# SCH.net
KiCad netlist of a schematic drawn in EasyEDA
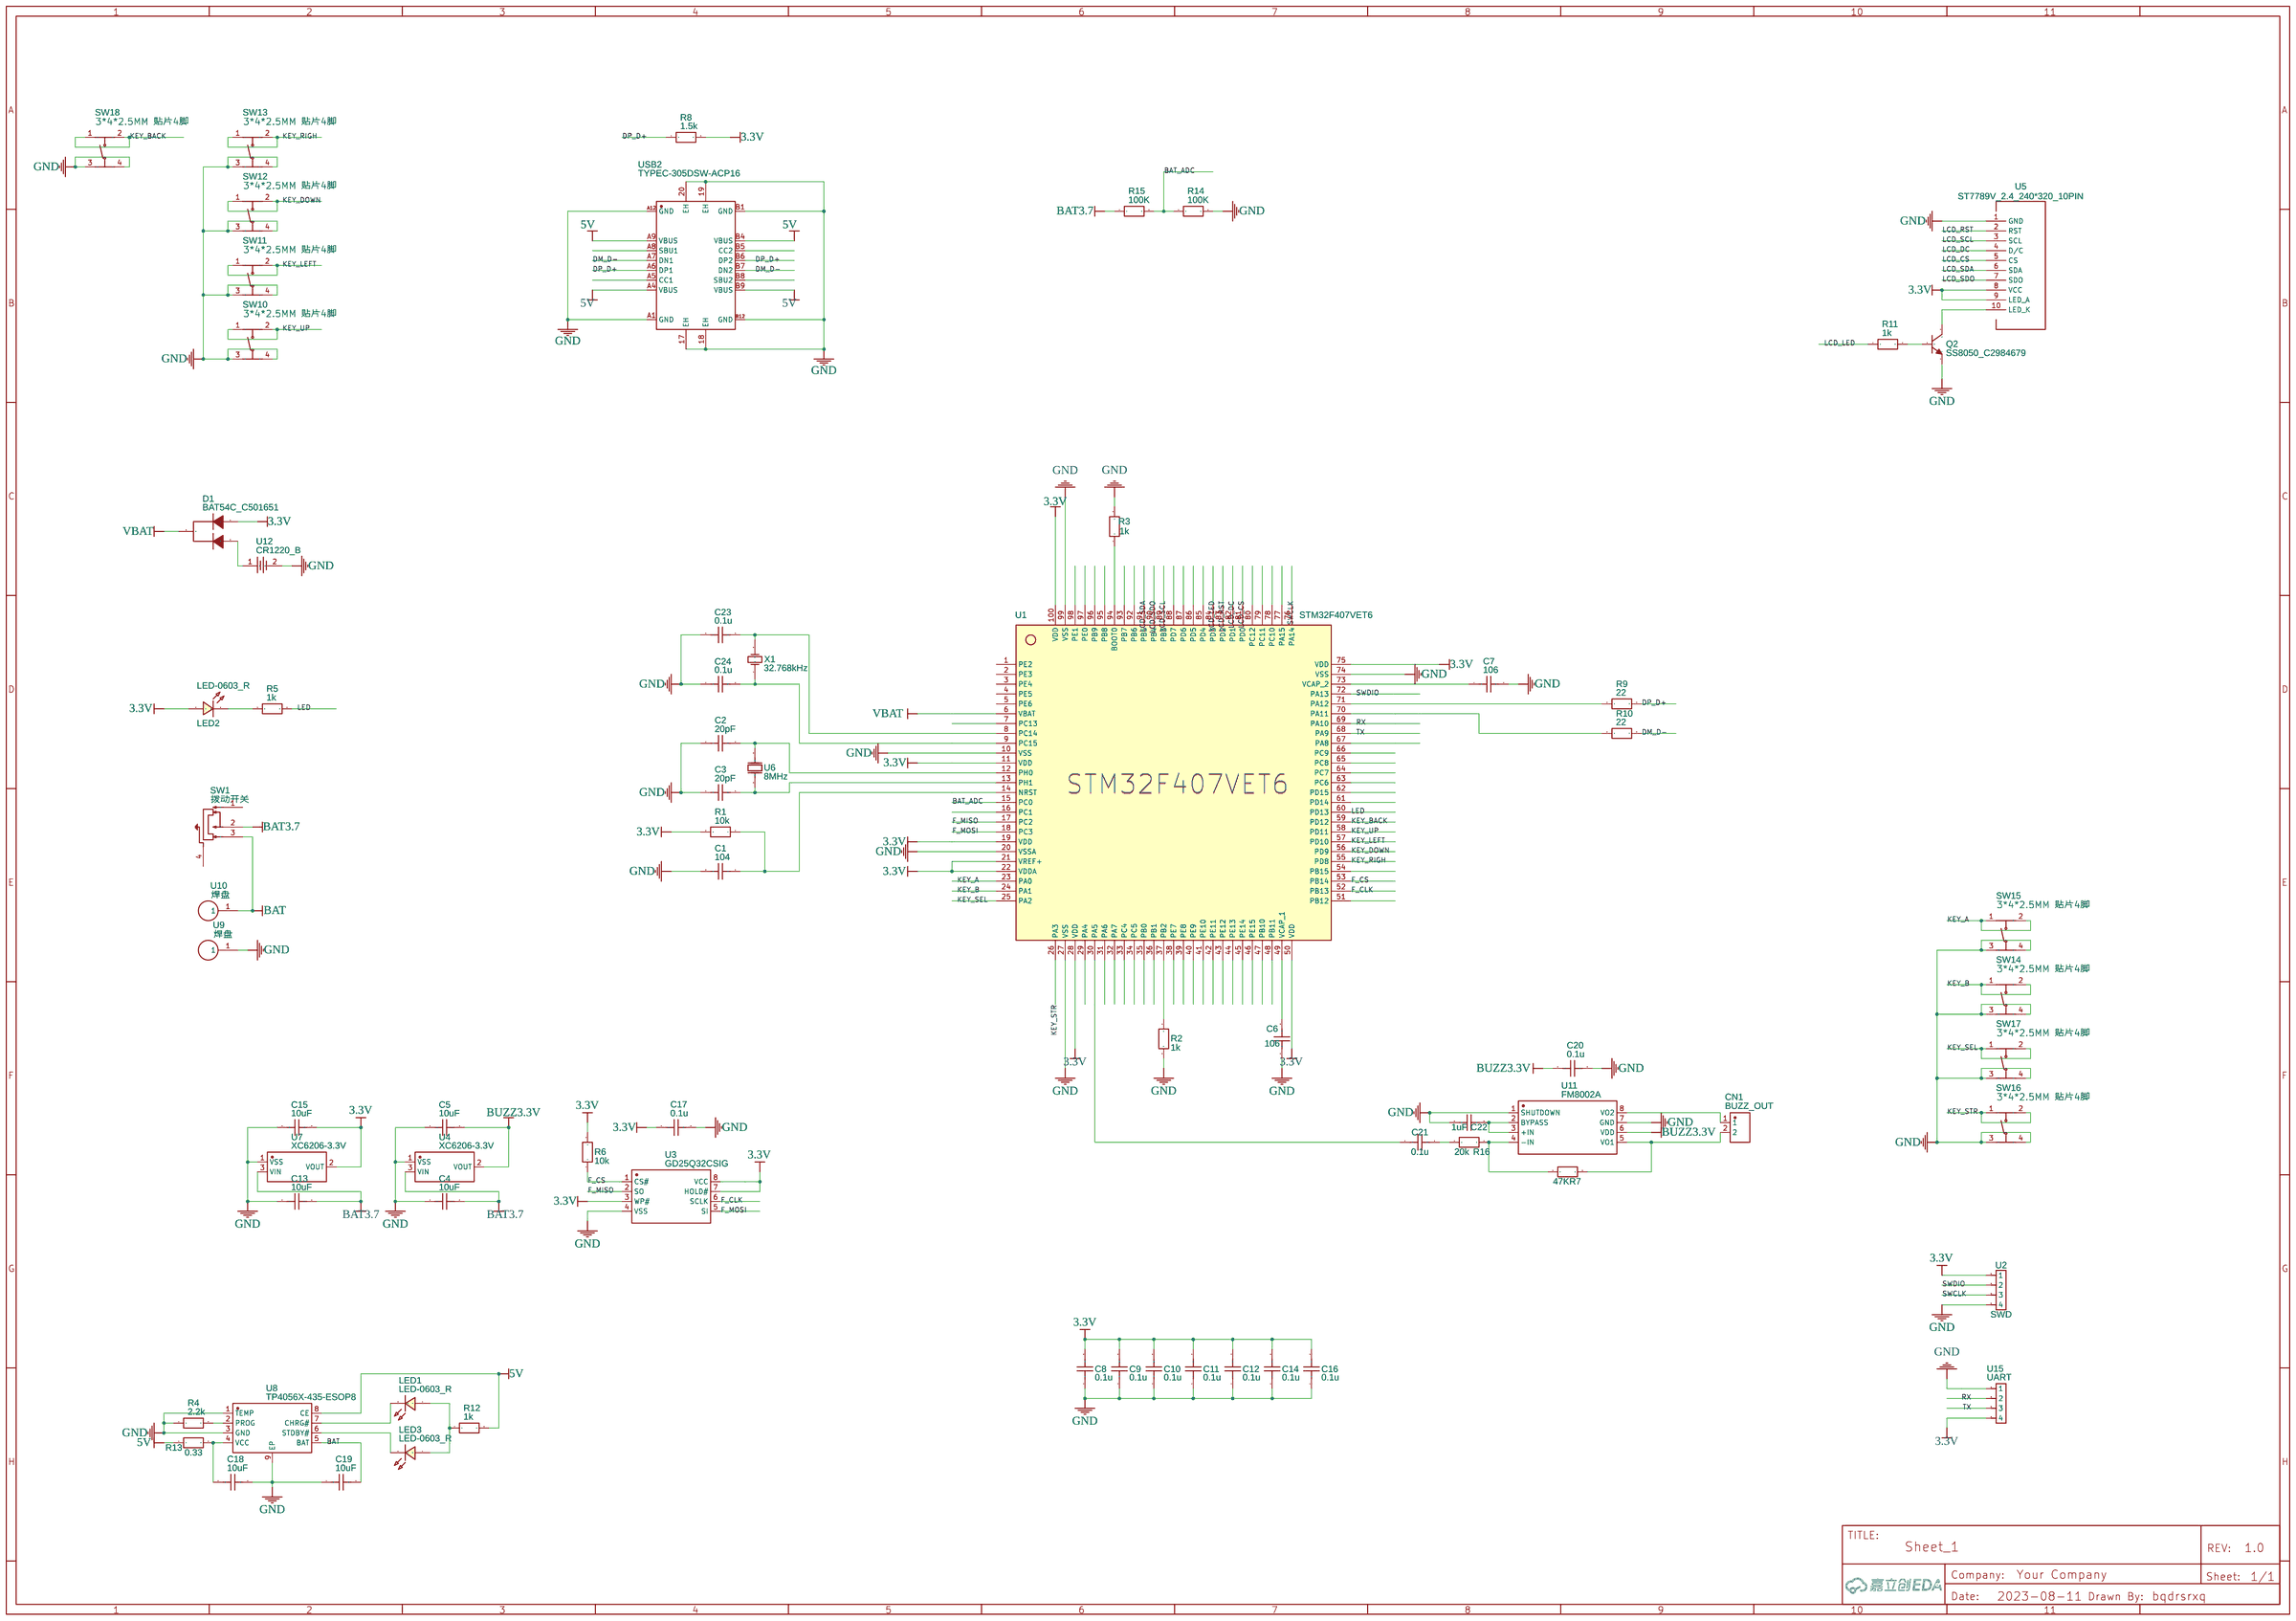
[diagram p0: schematic sheet]

(export (version "E")
  (design (tool "Eeschema 10.0.6"))
  (components
    (comp (ref "C1") (value "104") (libsource (lib "") (part "C_0603_US_2")))
    (comp (ref "C2") (value "20pF") (libsource (lib "") (part "C_0603_US")))
    (comp (ref "C3") (value "20pF") (libsource (lib "") (part "C_0603_US")))
    (comp (ref "C4") (value "10uF") (libsource (lib "") (part "C_0603_US")))
    (comp (ref "C5") (value "10uF") (libsource (lib "") (part "C_0603_US")))
    (comp (ref "C6") (value "106") (libsource (lib "") (part "C_0603_US_1")))
    (comp (ref "C7") (value "106") (libsource (lib "") (part "C_0603_US")))
    (comp (ref "C8") (value "0.1u") (libsource (lib "") (part "C_0603_US_1")))
    (comp (ref "C9") (value "0.1u") (libsource (lib "") (part "C_0603_US_1")))
    (comp (ref "C10") (value "0.1u") (libsource (lib "") (part "C_0603_US_1")))
    (comp (ref "C11") (value "0.1u") (libsource (lib "") (part "C_0603_US_1")))
    (comp (ref "C12") (value "0.1u") (libsource (lib "") (part "C_0603_US_1")))
    (comp (ref "C13") (value "10uF") (libsource (lib "") (part "C_0603_US")))
    (comp (ref "C14") (value "0.1u") (libsource (lib "") (part "C_0603_US_1")))
    (comp (ref "C15") (value "10uF") (libsource (lib "") (part "C_0603_US")))
    (comp (ref "C16") (value "0.1u") (libsource (lib "") (part "C_0603_US_1")))
    (comp (ref "C17") (value "0.1u") (libsource (lib "") (part "C_0603_US")))
    (comp (ref "C18") (value "10uF") (libsource (lib "") (part "C_0603_US")))
    (comp (ref "C19") (value "10uF") (libsource (lib "") (part "C_0603_US")))
    (comp (ref "C20") (value "0.1u") (libsource (lib "") (part "C_0603_US")))
    (comp (ref "C21") (value "0.1u") (libsource (lib "") (part "C_0603_US")))
    (comp (ref "C22") (value "1uF") (libsource (lib "") (part "C_0603_US")))
    (comp (ref "C23") (value "0.1u") (libsource (lib "") (part "C_0603_US")))
    (comp (ref "C24") (value "0.1u") (libsource (lib "") (part "C_0603_US")))
    (comp (ref "CN1")
      (value "BUZZ_OUT")
      (fields (field (name "Manufacturer Part") "CON2-2.54*2P"))
      (libsource (lib "") (part "CON2-2.54*2P"))
    )
    (comp (ref "D1")
      (value "BAT54C_C501651")
      (fields (field (name "Manufacturer Part") "BAT54C") (field (name "Manufacturer") "JF(吉福)"))
      (libsource (lib "") (part "BAT54C_C501651"))
    )
    (comp (ref "LED1")
      (value "LED-0603_R")
      (fields
        (field (name "BOM_Manufacturer Part") "19-217/R6C-AL1M2VY/3T")
        (field (name "BOM_Supplier Part") "C72044")
      )
      (libsource (lib "") (part "LED-0603_R_1"))
    )
    (comp (ref "LED2")
      (value "LED-0603_R")
      (fields
        (field (name "BOM_Manufacturer Part") "19-217/R6C-AL1M2VY/3T")
        (field (name "BOM_Supplier Part") "C72044")
      )
      (libsource (lib "") (part "LED-0603_R"))
    )
    (comp (ref "LED3")
      (value "LED-0603_R")
      (fields
        (field (name "BOM_Manufacturer Part") "19-217/R6C-AL1M2VY/3T")
        (field (name "BOM_Supplier Part") "C72044")
      )
      (libsource (lib "") (part "LED-0603_R_1"))
    )
    (comp (ref "Q2")
      (value "SS8050_C2984679")
      (fields (field (name "Manufacturer Part") "SS8050") (field (name "Manufacturer") "集晶电子"))
      (libsource (lib "") (part "SS8050_C2984679"))
    )
    (comp (ref "R1") (value "10k") (libsource (lib "") (part "R_0603_EU_2")))
    (comp (ref "R2") (value "1k") (libsource (lib "") (part "R_0603_EU_3")))
    (comp (ref "R3") (value "1k") (libsource (lib "") (part "R_0603_EU")))
    (comp (ref "R4") (value "2.2k") (libsource (lib "") (part "R_0603_EU_1")))
    (comp (ref "R5") (value "1k") (libsource (lib "") (part "R_0603_EU_1")))
    (comp (ref "R6") (value "10k") (libsource (lib "") (part "R_0603_EU")))
    (comp (ref "R7") (value "47K") (libsource (lib "") (part "R_0603_EU_1")))
    (comp (ref "R8") (value "1.5k") (libsource (lib "") (part "R_0603_EU_1")))
    (comp (ref "R9") (value "22") (libsource (lib "") (part "R_0603_EU_1")))
    (comp (ref "R10") (value "22") (libsource (lib "") (part "R_0603_EU_1")))
    (comp (ref "R11") (value "1k") (libsource (lib "") (part "R_0603_EU_1")))
    (comp (ref "R12") (value "1k") (libsource (lib "") (part "R_0603_EU_1")))
    (comp (ref "R13") (value "0.33") (libsource (lib "") (part "R_0603_EU_1")))
    (comp (ref "R14") (value "100K") (libsource (lib "") (part "R_0603_EU_1")))
    (comp (ref "R15") (value "100K") (libsource (lib "") (part "R_0603_EU_1")))
    (comp (ref "R16") (value "20k") (libsource (lib "") (part "R_0603_EU_1")))
    (comp (ref "SW1")
      (value "拨动开关")
      (fields
        (field (name "BOM_Manufacturer Part") "HX MSK12C02-BB")
        (field (name "BOM_Supplier Part") "C5149816")
      )
      (libsource (lib "") (part "拨动开关_三脚两档4固定_贴片_侧拨_MSK12C01"))
    )
    (comp (ref "SW10")
      (value "3*4*2.5MM 贴片4脚")
      (fields (field (name "Manufacturer Part") "3*4*2.5mm 贴片4脚"))
      (libsource (lib "") (part "3*4*2.5MM 贴片4脚"))
    )
    (comp (ref "SW11")
      (value "3*4*2.5MM 贴片4脚")
      (fields (field (name "Manufacturer Part") "3*4*2.5mm 贴片4脚"))
      (libsource (lib "") (part "3*4*2.5MM 贴片4脚"))
    )
    (comp (ref "SW12")
      (value "3*4*2.5MM 贴片4脚")
      (fields (field (name "Manufacturer Part") "3*4*2.5mm 贴片4脚"))
      (libsource (lib "") (part "3*4*2.5MM 贴片4脚"))
    )
    (comp (ref "SW13")
      (value "3*4*2.5MM 贴片4脚")
      (fields (field (name "Manufacturer Part") "3*4*2.5mm 贴片4脚"))
      (libsource (lib "") (part "3*4*2.5MM 贴片4脚"))
    )
    (comp (ref "SW14")
      (value "3*4*2.5MM 贴片4脚")
      (fields (field (name "Manufacturer Part") "3*4*2.5mm 贴片4脚"))
      (libsource (lib "") (part "3*4*2.5MM 贴片4脚"))
    )
    (comp (ref "SW15")
      (value "3*4*2.5MM 贴片4脚")
      (fields (field (name "Manufacturer Part") "3*4*2.5mm 贴片4脚"))
      (libsource (lib "") (part "3*4*2.5MM 贴片4脚"))
    )
    (comp (ref "SW16")
      (value "3*4*2.5MM 贴片4脚")
      (fields (field (name "Manufacturer Part") "3*4*2.5mm 贴片4脚"))
      (libsource (lib "") (part "3*4*2.5MM 贴片4脚"))
    )
    (comp (ref "SW17")
      (value "3*4*2.5MM 贴片4脚")
      (fields (field (name "Manufacturer Part") "3*4*2.5mm 贴片4脚"))
      (libsource (lib "") (part "3*4*2.5MM 贴片4脚"))
    )
    (comp (ref "SW18")
      (value "3*4*2.5MM 贴片4脚")
      (fields (field (name "Manufacturer Part") "3*4*2.5mm 贴片4脚"))
      (libsource (lib "") (part "3*4*2.5MM 贴片4脚"))
    )
    (comp (ref "U1") (value "STM32F407VET6") (libsource (lib "") (part "STM32F407VET6")))
    (comp (ref "U2") (value "SWD") (libsource (lib "") (part "CON4")))
    (comp (ref "U3")
      (value "GD25Q32CSIG")
      (fields (field (name "BOM_Supplier Part") "C79075"))
      (libsource (lib "") (part "GD25Q32CSIG"))
    )
    (comp (ref "U4")
      (value "XC6206-3.3V")
      (fields (field (name "BOM_Supplier Part") "C2891841"))
      (libsource (lib "") (part "XC6206-3.3V"))
    )
    (comp (ref "U5")
      (value "ST7789V_2.4_240*320_10PIN")
      (libsource (lib "") (part "ST7789V_2.4_240*320_10PIN"))
    )
    (comp (ref "U6")
      (value "8MHz")
      (fields (field (name "Manufacturer Part") "ATS08ASM-1E") (field (name "Manufacturer") "CTS(西迪斯)"))
      (libsource (lib "") (part "ATS08ASM-1E"))
    )
    (comp (ref "U7")
      (value "XC6206-3.3V")
      (fields (field (name "BOM_Supplier Part") "C2891841"))
      (libsource (lib "") (part "XC6206-3.3V"))
    )
    (comp (ref "U8") (value "TP4056X-435-ESOP8") (libsource (lib "") (part "TP4056X-435-ESOP8")))
    (comp (ref "U9") (value "焊盘") (libsource (lib "") (part "焊盘")))
    (comp (ref "U10") (value "焊盘") (libsource (lib "") (part "焊盘")))
    (comp (ref "U11")
      (value "FM8002A")
      (fields (field (name "Manufacturer") "FM(富满)"))
      (libsource (lib "") (part "FM8002A"))
    )
    (comp (ref "U12") (value "CR1220_B") (libsource (lib "") (part "CR1220_B")))
    (comp (ref "U15") (value "UART") (libsource (lib "") (part "CON4")))
    (comp (ref "USB2")
      (value "TYPEC-305DSW-ACP16")
      (fields (field (name "Manufacturer") "XUNPU(讯普)"))
      (libsource (lib "") (part "TYPEC-305DSW-ACP16"))
    )
    (comp (ref "X1")
      (value "32.768kHz")
      (fields (field (name "Manufacturer Part") "Q2632768PWNAC") (field (name "Manufacturer") "JYJE(晶友嘉)"))
      (libsource (lib "") (part "Q2632768PWNAC"))
    )
  )
  (nets
    (net (code "1") (name "/BAT_ADC") (class "Default")
      (node (ref "R14") (pin "1") (pinfunction "1_1") (pintype "unspecified"))
      (node (ref "R15") (pin "2") (pinfunction "2_2") (pintype "unspecified"))
      (node (ref "U1") (pin "15") (pinfunction "PC0_15") (pintype "unspecified"))
    )
    (net (code "2") (name "/DM_D-") (class "Default")
      (node (ref "R10") (pin "2") (pinfunction "2_2") (pintype "unspecified"))
      (node (ref "USB2") (pin "A7") (pinfunction "DN1_A7") (pintype "unspecified"))
      (node (ref "USB2") (pin "B7") (pinfunction "DN2_B7") (pintype "unspecified"))
    )
    (net (code "3") (name "/DP_D+") (class "Default")
      (node (ref "R8") (pin "1") (pinfunction "1_1") (pintype "unspecified"))
      (node (ref "R9") (pin "2") (pinfunction "2_2") (pintype "unspecified"))
      (node (ref "USB2") (pin "A6") (pinfunction "DP1_A6") (pintype "unspecified"))
      (node (ref "USB2") (pin "B6") (pinfunction "DP2_B6") (pintype "unspecified"))
    )
    (net (code "4") (name "/F_CLK") (class "Default")
      (node (ref "U1") (pin "52") (pinfunction "PB13_52") (pintype "unspecified"))
      (node (ref "U3") (pin "6") (pinfunction "SCLK_6") (pintype "unspecified"))
    )
    (net (code "5") (name "/F_CS") (class "Default")
      (node (ref "R6") (pin "1") (pinfunction "1_1") (pintype "unspecified"))
      (node (ref "U1") (pin "53") (pinfunction "PB14_53") (pintype "unspecified"))
      (node (ref "U3") (pin "1") (pinfunction "CS#_1") (pintype "unspecified"))
    )
    (net (code "6") (name "/F_MISO") (class "Default")
      (node (ref "U1") (pin "17") (pinfunction "PC2_17") (pintype "unspecified"))
      (node (ref "U3") (pin "2") (pinfunction "SO_2") (pintype "unspecified"))
    )
    (net (code "7") (name "/F_MOSI") (class "Default")
      (node (ref "U1") (pin "18") (pinfunction "PC3_18") (pintype "unspecified"))
      (node (ref "U3") (pin "5") (pinfunction "SI_5") (pintype "unspecified"))
    )
    (net (code "8") (name "/KEY_A") (class "Default")
      (node (ref "SW15") (pin "1") (pinfunction "1_1") (pintype "unspecified"))
      (node (ref "SW15") (pin "2") (pinfunction "2_2") (pintype "unspecified"))
      (node (ref "U1") (pin "23") (pinfunction "PA0_23") (pintype "unspecified"))
    )
    (net (code "9") (name "/KEY_B") (class "Default")
      (node (ref "SW14") (pin "1") (pinfunction "1_1") (pintype "unspecified"))
      (node (ref "SW14") (pin "2") (pinfunction "2_2") (pintype "unspecified"))
      (node (ref "U1") (pin "24") (pinfunction "PA1_24") (pintype "unspecified"))
    )
    (net (code "10") (name "/KEY_BACK") (class "Default")
      (node (ref "SW18") (pin "1") (pinfunction "1_1") (pintype "unspecified"))
      (node (ref "SW18") (pin "2") (pinfunction "2_2") (pintype "unspecified"))
      (node (ref "U1") (pin "59") (pinfunction "PD12_59") (pintype "unspecified"))
    )
    (net (code "11") (name "/KEY_DOWN") (class "Default")
      (node (ref "SW12") (pin "1") (pinfunction "1_1") (pintype "unspecified"))
      (node (ref "SW12") (pin "2") (pinfunction "2_2") (pintype "unspecified"))
      (node (ref "U1") (pin "56") (pinfunction "PD9_56") (pintype "unspecified"))
    )
    (net (code "12") (name "/KEY_LEFT") (class "Default")
      (node (ref "SW11") (pin "1") (pinfunction "1_1") (pintype "unspecified"))
      (node (ref "SW11") (pin "2") (pinfunction "2_2") (pintype "unspecified"))
      (node (ref "U1") (pin "57") (pinfunction "PD10_57") (pintype "unspecified"))
    )
    (net (code "13") (name "/KEY_RIGH") (class "Default")
      (node (ref "SW13") (pin "1") (pinfunction "1_1") (pintype "unspecified"))
      (node (ref "SW13") (pin "2") (pinfunction "2_2") (pintype "unspecified"))
      (node (ref "U1") (pin "55") (pinfunction "PD8_55") (pintype "unspecified"))
    )
    (net (code "14") (name "/KEY_SEL") (class "Default")
      (node (ref "SW17") (pin "1") (pinfunction "1_1") (pintype "unspecified"))
      (node (ref "SW17") (pin "2") (pinfunction "2_2") (pintype "unspecified"))
      (node (ref "U1") (pin "25") (pinfunction "PA2_25") (pintype "unspecified"))
    )
    (net (code "15") (name "/KEY_STR") (class "Default")
      (node (ref "SW16") (pin "1") (pinfunction "1_1") (pintype "unspecified"))
      (node (ref "SW16") (pin "2") (pinfunction "2_2") (pintype "unspecified"))
      (node (ref "U1") (pin "26") (pinfunction "PA3_26") (pintype "unspecified"))
    )
    (net (code "16") (name "/KEY_UP") (class "Default")
      (node (ref "SW10") (pin "1") (pinfunction "1_1") (pintype "unspecified"))
      (node (ref "SW10") (pin "2") (pinfunction "2_2") (pintype "unspecified"))
      (node (ref "U1") (pin "58") (pinfunction "PD11_58") (pintype "unspecified"))
    )
    (net (code "17") (name "/LCD_CS") (class "Default")
      (node (ref "U1") (pin "81") (pinfunction "PD0_81") (pintype "unspecified"))
      (node (ref "U5") (pin "5") (pinfunction "CS_5") (pintype "unspecified"))
    )
    (net (code "18") (name "/LCD_DC") (class "Default")
      (node (ref "U1") (pin "82") (pinfunction "PD1_82") (pintype "unspecified"))
      (node (ref "U5") (pin "4") (pinfunction "D/C_4") (pintype "unspecified"))
    )
    (net (code "19") (name "/LCD_LED") (class "Default")
      (node (ref "R11") (pin "1") (pinfunction "1_1") (pintype "unspecified"))
      (node (ref "U1") (pin "84") (pinfunction "PD3_84") (pintype "unspecified"))
    )
    (net (code "20") (name "/LCD_RST") (class "Default")
      (node (ref "U1") (pin "83") (pinfunction "PD2_83") (pintype "unspecified"))
      (node (ref "U5") (pin "2") (pinfunction "RST_2") (pintype "unspecified"))
    )
    (net (code "21") (name "/LCD_SCL") (class "Default")
      (node (ref "U1") (pin "89") (pinfunction "PB3_89") (pintype "unspecified"))
      (node (ref "U5") (pin "3") (pinfunction "SCL_3") (pintype "unspecified"))
    )
    (net (code "22") (name "/LCD_SDA") (class "Default")
      (node (ref "U1") (pin "91") (pinfunction "PB5_91") (pintype "unspecified"))
      (node (ref "U5") (pin "6") (pinfunction "SDA_6") (pintype "unspecified"))
    )
    (net (code "23") (name "/LCD_SDO") (class "Default")
      (node (ref "U1") (pin "90") (pinfunction "PB4_90") (pintype "unspecified"))
      (node (ref "U5") (pin "7") (pinfunction "SDO_7") (pintype "unspecified"))
    )
    (net (code "24") (name "/LED") (class "Default")
      (node (ref "R5") (pin "2") (pinfunction "2_2") (pintype "unspecified"))
      (node (ref "U1") (pin "60") (pinfunction "PD13_60") (pintype "unspecified"))
    )
    (net (code "25") (name "/RX") (class "Default")
      (node (ref "U1") (pin "69") (pinfunction "PA10_69") (pintype "unspecified"))
      (node (ref "U15") (pin "P$2") (pinfunction "2_P$2") (pintype "unspecified"))
    )
    (net (code "26") (name "/SWCLK") (class "Default")
      (node (ref "U1") (pin "76") (pinfunction "PA14_76") (pintype "unspecified"))
      (node (ref "U2") (pin "P$3") (pinfunction "3_P$3") (pintype "unspecified"))
    )
    (net (code "27") (name "/SWDIO") (class "Default")
      (node (ref "U1") (pin "72") (pinfunction "PA13_72") (pintype "unspecified"))
      (node (ref "U2") (pin "P$2") (pinfunction "2_P$2") (pintype "unspecified"))
    )
    (net (code "28") (name "/TX") (class "Default")
      (node (ref "U1") (pin "68") (pinfunction "PA9_68") (pintype "unspecified"))
      (node (ref "U15") (pin "P$3") (pinfunction "3_P$3") (pintype "unspecified"))
    )
    (net (code "29") (name "3.3V") (class "Default")
      (node (ref "C10") (pin "2") (pinfunction "2_2") (pintype "unspecified"))
      (node (ref "C11") (pin "2") (pinfunction "2_2") (pintype "unspecified"))
      (node (ref "C12") (pin "2") (pinfunction "2_2") (pintype "unspecified"))
      (node (ref "C14") (pin "2") (pinfunction "2_2") (pintype "unspecified"))
      (node (ref "C15") (pin "2") (pinfunction "2_2") (pintype "unspecified"))
      (node (ref "C16") (pin "2") (pinfunction "2_2") (pintype "unspecified"))
      (node (ref "C17") (pin "1") (pinfunction "1_1") (pintype "unspecified"))
      (node (ref "C8") (pin "2") (pinfunction "2_2") (pintype "unspecified"))
      (node (ref "C9") (pin "2") (pinfunction "2_2") (pintype "unspecified"))
      (node (ref "D1") (pin "2") (pinfunction "A2_2") (pintype "unspecified"))
      (node (ref "LED2") (pin "1") (pinfunction "1_1") (pintype "unspecified"))
      (node (ref "R1") (pin "2") (pinfunction "2_2") (pintype "unspecified"))
      (node (ref "R6") (pin "2") (pinfunction "2_2") (pintype "unspecified"))
      (node (ref "R8") (pin "2") (pinfunction "2_2") (pintype "unspecified"))
      (node (ref "U1") (pin "100") (pinfunction "VDD_100") (pintype "unspecified"))
      (node (ref "U1") (pin "11") (pinfunction "VDD_11") (pintype "unspecified"))
      (node (ref "U1") (pin "19") (pinfunction "VDD_19") (pintype "unspecified"))
      (node (ref "U1") (pin "21") (pinfunction "VREF+_21") (pintype "unspecified"))
      (node (ref "U1") (pin "22") (pinfunction "VDDA_22") (pintype "unspecified"))
      (node (ref "U1") (pin "28") (pinfunction "VDD_28") (pintype "unspecified"))
      (node (ref "U1") (pin "50") (pinfunction "VDD_50") (pintype "unspecified"))
      (node (ref "U1") (pin "75") (pinfunction "VDD_75") (pintype "unspecified"))
      (node (ref "U15") (pin "P$4") (pinfunction "4_P$4") (pintype "unspecified"))
      (node (ref "U2") (pin "P$1") (pinfunction "1_P$1") (pintype "unspecified"))
      (node (ref "U3") (pin "3") (pinfunction "WP#_3") (pintype "unspecified"))
      (node (ref "U3") (pin "7") (pinfunction "HOLD#_7") (pintype "unspecified"))
      (node (ref "U3") (pin "8") (pinfunction "VCC_8") (pintype "unspecified"))
      (node (ref "U5") (pin "8") (pinfunction "VCC_8") (pintype "unspecified"))
      (node (ref "U5") (pin "9") (pinfunction "LED_A_9") (pintype "unspecified"))
      (node (ref "U7") (pin "2") (pinfunction "VOUT_2") (pintype "unspecified"))
    )
    (net (code "30") (name "5V") (class "Default")
      (node (ref "R12") (pin "2") (pinfunction "2_2") (pintype "unspecified"))
      (node (ref "R13") (pin "1") (pinfunction "1_1") (pintype "unspecified"))
      (node (ref "U8") (pin "8") (pinfunction "CE_8") (pintype "unspecified"))
      (node (ref "USB2") (pin "A4") (pinfunction "VBUS_A4") (pintype "unspecified"))
      (node (ref "USB2") (pin "A9") (pinfunction "VBUS_A9") (pintype "unspecified"))
      (node (ref "USB2") (pin "B4") (pinfunction "VBUS_B4") (pintype "unspecified"))
      (node (ref "USB2") (pin "B9") (pinfunction "VBUS_B9") (pintype "unspecified"))
    )
    (net (code "31") (name "BAT") (class "Default")
      (node (ref "C19") (pin "2") (pinfunction "2_2") (pintype "unspecified"))
      (node (ref "SW1") (pin "3") (pinfunction "3_3") (pintype "unspecified"))
      (node (ref "U10") (pin "1") (pinfunction "1_1") (pintype "unspecified"))
      (node (ref "U8") (pin "5") (pinfunction "BAT_5") (pintype "unspecified"))
    )
    (net (code "32") (name "BAT3.7") (class "Default")
      (node (ref "C13") (pin "2") (pinfunction "2_2") (pintype "unspecified"))
      (node (ref "C4") (pin "2") (pinfunction "2_2") (pintype "unspecified"))
      (node (ref "R15") (pin "1") (pinfunction "1_1") (pintype "unspecified"))
      (node (ref "SW1") (pin "2") (pinfunction "2_2") (pintype "unspecified"))
      (node (ref "U4") (pin "3") (pinfunction "VIN_3") (pintype "unspecified"))
      (node (ref "U7") (pin "3") (pinfunction "VIN_3") (pintype "unspecified"))
    )
    (net (code "33") (name "BUZZ3.3V") (class "Default")
      (node (ref "C20") (pin "1") (pinfunction "1_1") (pintype "unspecified"))
      (node (ref "C5") (pin "2") (pinfunction "2_2") (pintype "unspecified"))
      (node (ref "U11") (pin "6") (pinfunction "VDD_6") (pintype "unspecified"))
      (node (ref "U4") (pin "2") (pinfunction "VOUT_2") (pintype "unspecified"))
    )
    (net (code "34") (name "GND") (class "Default")
      (node (ref "C1") (pin "2") (pinfunction "2_2") (pintype "unspecified"))
      (node (ref "C10") (pin "1") (pinfunction "1_1") (pintype "unspecified"))
      (node (ref "C11") (pin "1") (pinfunction "1_1") (pintype "unspecified"))
      (node (ref "C12") (pin "1") (pinfunction "1_1") (pintype "unspecified"))
      (node (ref "C13") (pin "1") (pinfunction "1_1") (pintype "unspecified"))
      (node (ref "C14") (pin "1") (pinfunction "1_1") (pintype "unspecified"))
      (node (ref "C15") (pin "1") (pinfunction "1_1") (pintype "unspecified"))
      (node (ref "C16") (pin "1") (pinfunction "1_1") (pintype "unspecified"))
      (node (ref "C17") (pin "2") (pinfunction "2_2") (pintype "unspecified"))
      (node (ref "C18") (pin "2") (pinfunction "2_2") (pintype "unspecified"))
      (node (ref "C19") (pin "1") (pinfunction "1_1") (pintype "unspecified"))
      (node (ref "C2") (pin "1") (pinfunction "1_1") (pintype "unspecified"))
      (node (ref "C20") (pin "2") (pinfunction "2_2") (pintype "unspecified"))
      (node (ref "C22") (pin "1") (pinfunction "1_1") (pintype "unspecified"))
      (node (ref "C23") (pin "1") (pinfunction "1_1") (pintype "unspecified"))
      (node (ref "C24") (pin "1") (pinfunction "1_1") (pintype "unspecified"))
      (node (ref "C3") (pin "1") (pinfunction "1_1") (pintype "unspecified"))
      (node (ref "C4") (pin "1") (pinfunction "1_1") (pintype "unspecified"))
      (node (ref "C5") (pin "1") (pinfunction "1_1") (pintype "unspecified"))
      (node (ref "C6") (pin "1") (pinfunction "1_1") (pintype "unspecified"))
      (node (ref "C7") (pin "2") (pinfunction "2_2") (pintype "unspecified"))
      (node (ref "C8") (pin "1") (pinfunction "1_1") (pintype "unspecified"))
      (node (ref "C9") (pin "1") (pinfunction "1_1") (pintype "unspecified"))
      (node (ref "Q2") (pin "2") (pinfunction "E_2") (pintype "input"))
      (node (ref "R14") (pin "2") (pinfunction "2_2") (pintype "unspecified"))
      (node (ref "R2") (pin "2") (pinfunction "2_2") (pintype "unspecified"))
      (node (ref "R3") (pin "2") (pinfunction "2_2") (pintype "unspecified"))
      (node (ref "R4") (pin "1") (pinfunction "1_1") (pintype "unspecified"))
      (node (ref "SW10") (pin "3") (pinfunction "3_3") (pintype "unspecified"))
      (node (ref "SW10") (pin "4") (pinfunction "4_4") (pintype "unspecified"))
      (node (ref "SW11") (pin "3") (pinfunction "3_3") (pintype "unspecified"))
      (node (ref "SW11") (pin "4") (pinfunction "4_4") (pintype "unspecified"))
      (node (ref "SW12") (pin "3") (pinfunction "3_3") (pintype "unspecified"))
      (node (ref "SW12") (pin "4") (pinfunction "4_4") (pintype "unspecified"))
      (node (ref "SW13") (pin "3") (pinfunction "3_3") (pintype "unspecified"))
      (node (ref "SW13") (pin "4") (pinfunction "4_4") (pintype "unspecified"))
      (node (ref "SW14") (pin "3") (pinfunction "3_3") (pintype "unspecified"))
      (node (ref "SW14") (pin "4") (pinfunction "4_4") (pintype "unspecified"))
      (node (ref "SW15") (pin "3") (pinfunction "3_3") (pintype "unspecified"))
      (node (ref "SW15") (pin "4") (pinfunction "4_4") (pintype "unspecified"))
      (node (ref "SW16") (pin "3") (pinfunction "3_3") (pintype "unspecified"))
      (node (ref "SW16") (pin "4") (pinfunction "4_4") (pintype "unspecified"))
      (node (ref "SW17") (pin "3") (pinfunction "3_3") (pintype "unspecified"))
      (node (ref "SW17") (pin "4") (pinfunction "4_4") (pintype "unspecified"))
      (node (ref "SW18") (pin "3") (pinfunction "3_3") (pintype "unspecified"))
      (node (ref "SW18") (pin "4") (pinfunction "4_4") (pintype "unspecified"))
      (node (ref "U1") (pin "10") (pinfunction "VSS_10") (pintype "unspecified"))
      (node (ref "U1") (pin "20") (pinfunction "VSSA_20") (pintype "unspecified"))
      (node (ref "U1") (pin "27") (pinfunction "VSS_27") (pintype "unspecified"))
      (node (ref "U1") (pin "74") (pinfunction "VSS_74") (pintype "unspecified"))
      (node (ref "U1") (pin "99") (pinfunction "VSS_99") (pintype "unspecified"))
      (node (ref "U11") (pin "1") (pinfunction "SHUTDOWN_1") (pintype "unspecified"))
      (node (ref "U11") (pin "7") (pinfunction "GND_7") (pintype "unspecified"))
      (node (ref "U12") (pin "2") (pinfunction "2_2") (pintype "input"))
      (node (ref "U15") (pin "P$1") (pinfunction "1_P$1") (pintype "unspecified"))
      (node (ref "U2") (pin "P$4") (pinfunction "4_P$4") (pintype "unspecified"))
      (node (ref "U3") (pin "4") (pinfunction "VSS_4") (pintype "unspecified"))
      (node (ref "U4") (pin "1") (pinfunction "VSS_1") (pintype "unspecified"))
      (node (ref "U5") (pin "1") (pinfunction "GND_1") (pintype "unspecified"))
      (node (ref "U7") (pin "1") (pinfunction "VSS_1") (pintype "unspecified"))
      (node (ref "U8") (pin "1") (pinfunction "TEMP_1") (pintype "unspecified"))
      (node (ref "U8") (pin "3") (pinfunction "GND_3") (pintype "unspecified"))
      (node (ref "U8") (pin "9") (pinfunction "EP_9") (pintype "unspecified"))
      (node (ref "U9") (pin "1") (pinfunction "1_1") (pintype "unspecified"))
      (node (ref "USB2") (pin "17") (pinfunction "EH_17") (pintype "unspecified"))
      (node (ref "USB2") (pin "18") (pinfunction "EH_18") (pintype "unspecified"))
      (node (ref "USB2") (pin "19") (pinfunction "EH_19") (pintype "unspecified"))
      (node (ref "USB2") (pin "20") (pinfunction "EH_20") (pintype "unspecified"))
      (node (ref "USB2") (pin "A1") (pinfunction "GND_A1") (pintype "unspecified"))
      (node (ref "USB2") (pin "A12") (pinfunction "GND_A12") (pintype "unspecified"))
      (node (ref "USB2") (pin "B1") (pinfunction "GND_B1") (pintype "unspecified"))
      (node (ref "USB2") (pin "B12") (pinfunction "GND_B12") (pintype "unspecified"))
    )
    (net (code "35") (name "Net-(C21-Pad2)") (class "Default")
      (node (ref "C21") (pin "2") (pinfunction "2_2") (pintype "unspecified"))
      (node (ref "R16") (pin "1") (pinfunction "1_1") (pintype "unspecified"))
    )
    (net (code "36") (name "Net-(D1-A1)") (class "Default")
      (node (ref "D1") (pin "1") (pinfunction "A1_1") (pintype "unspecified"))
      (node (ref "U12") (pin "1") (pinfunction "1_1") (pintype "input"))
    )
    (net (code "37") (name "Net-(LED1-Pad1)") (class "Default")
      (node (ref "LED1") (pin "1") (pinfunction "1_1") (pintype "unspecified"))
      (node (ref "LED3") (pin "1") (pinfunction "1_1") (pintype "unspecified"))
      (node (ref "R12") (pin "1") (pinfunction "1_1") (pintype "unspecified"))
    )
    (net (code "38") (name "Net-(LED2-Pad2)") (class "Default")
      (node (ref "LED2") (pin "2") (pinfunction "2_2") (pintype "unspecified"))
      (node (ref "R5") (pin "1") (pinfunction "1_1") (pintype "unspecified"))
    )
    (net (code "39") (name "Net-(Q2-B)") (class "Default")
      (node (ref "Q2") (pin "1") (pinfunction "B_1") (pintype "input"))
      (node (ref "R11") (pin "2") (pinfunction "2_2") (pintype "unspecified"))
    )
    (net (code "40") (name "Net-(Q2-C)") (class "Default")
      (node (ref "Q2") (pin "3") (pinfunction "C_3") (pintype "input"))
      (node (ref "U5") (pin "10") (pinfunction "LED_K_10") (pintype "unspecified"))
    )
    (net (code "41") (name "Net-(U1-BOOT0)") (class "Default")
      (node (ref "R3") (pin "1") (pinfunction "1_1") (pintype "unspecified"))
      (node (ref "U1") (pin "94") (pinfunction "BOOT0_94") (pintype "unspecified"))
    )
    (net (code "42") (name "Net-(U1-NRST)") (class "Default")
      (node (ref "C1") (pin "1") (pinfunction "1_1") (pintype "unspecified"))
      (node (ref "R1") (pin "1") (pinfunction "1_1") (pintype "unspecified"))
      (node (ref "U1") (pin "14") (pinfunction "NRST_14") (pintype "unspecified"))
    )
    (net (code "43") (name "Net-(U1-PA5)") (class "Default")
      (node (ref "C21") (pin "1") (pinfunction "1_1") (pintype "unspecified"))
      (node (ref "U1") (pin "30") (pinfunction "PA5_30") (pintype "unspecified"))
    )
    (net (code "44") (name "Net-(U1-PA11)") (class "Default")
      (node (ref "R10") (pin "1") (pinfunction "1_1") (pintype "unspecified"))
      (node (ref "U1") (pin "70") (pinfunction "PA11_70") (pintype "unspecified"))
    )
    (net (code "45") (name "Net-(U1-PA12)") (class "Default")
      (node (ref "R9") (pin "1") (pinfunction "1_1") (pintype "unspecified"))
      (node (ref "U1") (pin "71") (pinfunction "PA12_71") (pintype "unspecified"))
    )
    (net (code "46") (name "Net-(U1-PB2)") (class "Default")
      (node (ref "R2") (pin "1") (pinfunction "1_1") (pintype "unspecified"))
      (node (ref "U1") (pin "37") (pinfunction "PB2_37") (pintype "unspecified"))
    )
    (net (code "47") (name "Net-(U1-PC14)") (class "Default")
      (node (ref "C23") (pin "2") (pinfunction "2_2") (pintype "unspecified"))
      (node (ref "U1") (pin "8") (pinfunction "PC14_8") (pintype "unspecified"))
      (node (ref "X1") (pin "2") (pinfunction "OSC2_2") (pintype "unspecified"))
    )
    (net (code "48") (name "Net-(U1-PC15)") (class "Default")
      (node (ref "C24") (pin "2") (pinfunction "2_2") (pintype "unspecified"))
      (node (ref "U1") (pin "9") (pinfunction "PC15_9") (pintype "unspecified"))
      (node (ref "X1") (pin "1") (pinfunction "OSC1_1") (pintype "unspecified"))
    )
    (net (code "49") (name "Net-(U1-PH0)") (class "Default")
      (node (ref "C2") (pin "2") (pinfunction "2_2") (pintype "unspecified"))
      (node (ref "U1") (pin "12") (pinfunction "PH0_12") (pintype "unspecified"))
      (node (ref "U6") (pin "2") (pinfunction "OSC2_2") (pintype "input"))
    )
    (net (code "50") (name "Net-(U1-PH1)") (class "Default")
      (node (ref "C3") (pin "2") (pinfunction "2_2") (pintype "unspecified"))
      (node (ref "U1") (pin "13") (pinfunction "PH1_13") (pintype "unspecified"))
      (node (ref "U6") (pin "1") (pinfunction "OSC1_1") (pintype "input"))
    )
    (net (code "51") (name "Net-(U1-VCAP_1)") (class "Default")
      (node (ref "C6") (pin "2") (pinfunction "2_2") (pintype "unspecified"))
      (node (ref "U1") (pin "49") (pinfunction "VCAP_1_49") (pintype "unspecified"))
    )
    (net (code "52") (name "Net-(U1-VCAP_2)") (class "Default")
      (node (ref "C7") (pin "1") (pinfunction "1_1") (pintype "unspecified"))
      (node (ref "U1") (pin "73") (pinfunction "VCAP_2_73") (pintype "unspecified"))
    )
    (net (code "53") (name "Net-(U8-CHRG#)") (class "Default")
      (node (ref "LED1") (pin "2") (pinfunction "2_2") (pintype "unspecified"))
      (node (ref "U8") (pin "7") (pinfunction "CHRG#_7") (pintype "unspecified"))
    )
    (net (code "54") (name "Net-(U8-PROG)") (class "Default")
      (node (ref "R4") (pin "2") (pinfunction "2_2") (pintype "unspecified"))
      (node (ref "U8") (pin "2") (pinfunction "PROG_2") (pintype "unspecified"))
    )
    (net (code "55") (name "Net-(U8-STDBY#)") (class "Default")
      (node (ref "LED3") (pin "2") (pinfunction "2_2") (pintype "unspecified"))
      (node (ref "U8") (pin "6") (pinfunction "STDBY#_6") (pintype "unspecified"))
    )
    (net (code "56") (name "Net-(U8-VCC)") (class "Default")
      (node (ref "C18") (pin "1") (pinfunction "1_1") (pintype "unspecified"))
      (node (ref "R13") (pin "2") (pinfunction "2_2") (pintype "unspecified"))
      (node (ref "U8") (pin "4") (pinfunction "VCC_4") (pintype "unspecified"))
    )
    (net (code "57") (name "Net-(U11-+IN)") (class "Default")
      (node (ref "C22") (pin "2") (pinfunction "2_2") (pintype "unspecified"))
      (node (ref "U11") (pin "2") (pinfunction "BYPASS_2") (pintype "unspecified"))
      (node (ref "U11") (pin "3") (pinfunction "+IN_3") (pintype "unspecified"))
    )
    (net (code "58") (name "Net-(U11--IN)") (class "Default")
      (node (ref "R16") (pin "2") (pinfunction "2_2") (pintype "unspecified"))
      (node (ref "R7") (pin "1") (pinfunction "1_1") (pintype "unspecified"))
      (node (ref "U11") (pin "4") (pinfunction "-IN_4") (pintype "unspecified"))
    )
    (net (code "59") (name "Net-(U11-VO1)") (class "Default")
      (node (ref "CN1") (pin "2") (pinfunction "2_2") (pintype "unspecified"))
      (node (ref "R7") (pin "2") (pinfunction "2_2") (pintype "unspecified"))
      (node (ref "U11") (pin "5") (pinfunction "VO1_5") (pintype "unspecified"))
    )
    (net (code "60") (name "Net-(U11-VO2)") (class "Default")
      (node (ref "CN1") (pin "1") (pinfunction "1_1") (pintype "unspecified"))
      (node (ref "U11") (pin "8") (pinfunction "VO2_8") (pintype "unspecified"))
    )
    (net (code "61") (name "VBAT") (class "Default")
      (node (ref "D1") (pin "3") (pinfunction "K_3") (pintype "unspecified"))
      (node (ref "U1") (pin "6") (pinfunction "VBAT_6") (pintype "unspecified"))
    )
    (net (code "62") (name "unconnected-(SW1-Pad1)") (class "Default")
      (node (ref "SW1") (pin "1") (pinfunction "1_1") (pintype "unspecified"))
    )
    (net (code "63") (name "unconnected-(SW1-Pad4)") (class "Default")
      (node (ref "SW1") (pin "4") (pinfunction "4_4") (pintype "unspecified"))
    )
    (net (code "64") (name "unconnected-(U1-PA4-Pad29)") (class "Default")
      (node (ref "U1") (pin "29") (pinfunction "PA4_29") (pintype "unspecified"))
    )
    (net (code "65") (name "unconnected-(U1-PA6-Pad31)") (class "Default")
      (node (ref "U1") (pin "31") (pinfunction "PA6_31") (pintype "unspecified"))
    )
    (net (code "66") (name "unconnected-(U1-PA7-Pad32)") (class "Default")
      (node (ref "U1") (pin "32") (pinfunction "PA7_32") (pintype "unspecified"))
    )
    (net (code "67") (name "unconnected-(U1-PA8-Pad67)") (class "Default")
      (node (ref "U1") (pin "67") (pinfunction "PA8_67") (pintype "unspecified"))
    )
    (net (code "68") (name "unconnected-(U1-PA15-Pad77)") (class "Default")
      (node (ref "U1") (pin "77") (pinfunction "PA15_77") (pintype "unspecified"))
    )
    (net (code "69") (name "unconnected-(U1-PB0-Pad35)") (class "Default")
      (node (ref "U1") (pin "35") (pinfunction "PB0_35") (pintype "unspecified"))
    )
    (net (code "70") (name "unconnected-(U1-PB1-Pad36)") (class "Default")
      (node (ref "U1") (pin "36") (pinfunction "PB1_36") (pintype "unspecified"))
    )
    (net (code "71") (name "unconnected-(U1-PB6-Pad92)") (class "Default")
      (node (ref "U1") (pin "92") (pinfunction "PB6_92") (pintype "unspecified"))
    )
    (net (code "72") (name "unconnected-(U1-PB7-Pad93)") (class "Default")
      (node (ref "U1") (pin "93") (pinfunction "PB7_93") (pintype "unspecified"))
    )
    (net (code "73") (name "unconnected-(U1-PB8-Pad95)") (class "Default")
      (node (ref "U1") (pin "95") (pinfunction "PB8_95") (pintype "unspecified"))
    )
    (net (code "74") (name "unconnected-(U1-PB9-Pad96)") (class "Default")
      (node (ref "U1") (pin "96") (pinfunction "PB9_96") (pintype "unspecified"))
    )
    (net (code "75") (name "unconnected-(U1-PB10-Pad47)") (class "Default")
      (node (ref "U1") (pin "47") (pinfunction "PB10_47") (pintype "unspecified"))
    )
    (net (code "76") (name "unconnected-(U1-PB11-Pad48)") (class "Default")
      (node (ref "U1") (pin "48") (pinfunction "PB11_48") (pintype "unspecified"))
    )
    (net (code "77") (name "unconnected-(U1-PB12-Pad51)") (class "Default")
      (node (ref "U1") (pin "51") (pinfunction "PB12_51") (pintype "unspecified"))
    )
    (net (code "78") (name "unconnected-(U1-PB15-Pad54)") (class "Default")
      (node (ref "U1") (pin "54") (pinfunction "PB15_54") (pintype "unspecified"))
    )
    (net (code "79") (name "unconnected-(U1-PC1-Pad16)") (class "Default")
      (node (ref "U1") (pin "16") (pinfunction "PC1_16") (pintype "unspecified"))
    )
    (net (code "80") (name "unconnected-(U1-PC4-Pad33)") (class "Default")
      (node (ref "U1") (pin "33") (pinfunction "PC4_33") (pintype "unspecified"))
    )
    (net (code "81") (name "unconnected-(U1-PC5-Pad34)") (class "Default")
      (node (ref "U1") (pin "34") (pinfunction "PC5_34") (pintype "unspecified"))
    )
    (net (code "82") (name "unconnected-(U1-PC6-Pad63)") (class "Default")
      (node (ref "U1") (pin "63") (pinfunction "PC6_63") (pintype "unspecified"))
    )
    (net (code "83") (name "unconnected-(U1-PC7-Pad64)") (class "Default")
      (node (ref "U1") (pin "64") (pinfunction "PC7_64") (pintype "unspecified"))
    )
    (net (code "84") (name "unconnected-(U1-PC8-Pad65)") (class "Default")
      (node (ref "U1") (pin "65") (pinfunction "PC8_65") (pintype "unspecified"))
    )
    (net (code "85") (name "unconnected-(U1-PC9-Pad66)") (class "Default")
      (node (ref "U1") (pin "66") (pinfunction "PC9_66") (pintype "unspecified"))
    )
    (net (code "86") (name "unconnected-(U1-PC10-Pad78)") (class "Default")
      (node (ref "U1") (pin "78") (pinfunction "PC10_78") (pintype "unspecified"))
    )
    (net (code "87") (name "unconnected-(U1-PC11-Pad79)") (class "Default")
      (node (ref "U1") (pin "79") (pinfunction "PC11_79") (pintype "unspecified"))
    )
    (net (code "88") (name "unconnected-(U1-PC12-Pad80)") (class "Default")
      (node (ref "U1") (pin "80") (pinfunction "PC12_80") (pintype "unspecified"))
    )
    (net (code "89") (name "unconnected-(U1-PC13-Pad7)") (class "Default")
      (node (ref "U1") (pin "7") (pinfunction "PC13_7") (pintype "unspecified"))
    )
    (net (code "90") (name "unconnected-(U1-PD4-Pad85)") (class "Default")
      (node (ref "U1") (pin "85") (pinfunction "PD4_85") (pintype "unspecified"))
    )
    (net (code "91") (name "unconnected-(U1-PD5-Pad86)") (class "Default")
      (node (ref "U1") (pin "86") (pinfunction "PD5_86") (pintype "unspecified"))
    )
    (net (code "92") (name "unconnected-(U1-PD6-Pad87)") (class "Default")
      (node (ref "U1") (pin "87") (pinfunction "PD6_87") (pintype "unspecified"))
    )
    (net (code "93") (name "unconnected-(U1-PD7-Pad88)") (class "Default")
      (node (ref "U1") (pin "88") (pinfunction "PD7_88") (pintype "unspecified"))
    )
    (net (code "94") (name "unconnected-(U1-PD14-Pad61)") (class "Default")
      (node (ref "U1") (pin "61") (pinfunction "PD14_61") (pintype "unspecified"))
    )
    (net (code "95") (name "unconnected-(U1-PD15-Pad62)") (class "Default")
      (node (ref "U1") (pin "62") (pinfunction "PD15_62") (pintype "unspecified"))
    )
    (net (code "96") (name "unconnected-(U1-PE0-Pad97)") (class "Default")
      (node (ref "U1") (pin "97") (pinfunction "PE0_97") (pintype "unspecified"))
    )
    (net (code "97") (name "unconnected-(U1-PE1-Pad98)") (class "Default")
      (node (ref "U1") (pin "98") (pinfunction "PE1_98") (pintype "unspecified"))
    )
    (net (code "98") (name "unconnected-(U1-PE2-Pad1)") (class "Default")
      (node (ref "U1") (pin "1") (pinfunction "PE2_1") (pintype "unspecified"))
    )
    (net (code "99") (name "unconnected-(U1-PE3-Pad2)") (class "Default")
      (node (ref "U1") (pin "2") (pinfunction "PE3_2") (pintype "unspecified"))
    )
    (net (code "100") (name "unconnected-(U1-PE4-Pad3)") (class "Default")
      (node (ref "U1") (pin "3") (pinfunction "PE4_3") (pintype "unspecified"))
    )
    (net (code "101") (name "unconnected-(U1-PE5-Pad4)") (class "Default")
      (node (ref "U1") (pin "4") (pinfunction "PE5_4") (pintype "unspecified"))
    )
    (net (code "102") (name "unconnected-(U1-PE6-Pad5)") (class "Default")
      (node (ref "U1") (pin "5") (pinfunction "PE6_5") (pintype "unspecified"))
    )
    (net (code "103") (name "unconnected-(U1-PE7-Pad38)") (class "Default")
      (node (ref "U1") (pin "38") (pinfunction "PE7_38") (pintype "unspecified"))
    )
    (net (code "104") (name "unconnected-(U1-PE8-Pad39)") (class "Default")
      (node (ref "U1") (pin "39") (pinfunction "PE8_39") (pintype "unspecified"))
    )
    (net (code "105") (name "unconnected-(U1-PE9-Pad40)") (class "Default")
      (node (ref "U1") (pin "40") (pinfunction "PE9_40") (pintype "unspecified"))
    )
    (net (code "106") (name "unconnected-(U1-PE10-Pad41)") (class "Default")
      (node (ref "U1") (pin "41") (pinfunction "PE10_41") (pintype "unspecified"))
    )
    (net (code "107") (name "unconnected-(U1-PE11-Pad42)") (class "Default")
      (node (ref "U1") (pin "42") (pinfunction "PE11_42") (pintype "unspecified"))
    )
    (net (code "108") (name "unconnected-(U1-PE12-Pad43)") (class "Default")
      (node (ref "U1") (pin "43") (pinfunction "PE12_43") (pintype "unspecified"))
    )
    (net (code "109") (name "unconnected-(U1-PE13-Pad44)") (class "Default")
      (node (ref "U1") (pin "44") (pinfunction "PE13_44") (pintype "unspecified"))
    )
    (net (code "110") (name "unconnected-(U1-PE14-Pad45)") (class "Default")
      (node (ref "U1") (pin "45") (pinfunction "PE14_45") (pintype "unspecified"))
    )
    (net (code "111") (name "unconnected-(U1-PE15-Pad46)") (class "Default")
      (node (ref "U1") (pin "46") (pinfunction "PE15_46") (pintype "unspecified"))
    )
    (net (code "112") (name "unconnected-(USB2-CC1-PadA5)") (class "Default")
      (node (ref "USB2") (pin "A5") (pinfunction "CC1_A5") (pintype "unspecified"))
    )
    (net (code "113") (name "unconnected-(USB2-CC2-PadB5)") (class "Default")
      (node (ref "USB2") (pin "B5") (pinfunction "CC2_B5") (pintype "unspecified"))
    )
    (net (code "114") (name "unconnected-(USB2-SBU1-PadA8)") (class "Default")
      (node (ref "USB2") (pin "A8") (pinfunction "SBU1_A8") (pintype "unspecified"))
    )
    (net (code "115") (name "unconnected-(USB2-SBU2-PadB8)") (class "Default")
      (node (ref "USB2") (pin "B8") (pinfunction "SBU2_B8") (pintype "unspecified"))
    )
  )
)
